# 2020_IST_Respirator_SMD_v3.net
KiCad netlist of a schematic drawn in EAGLE
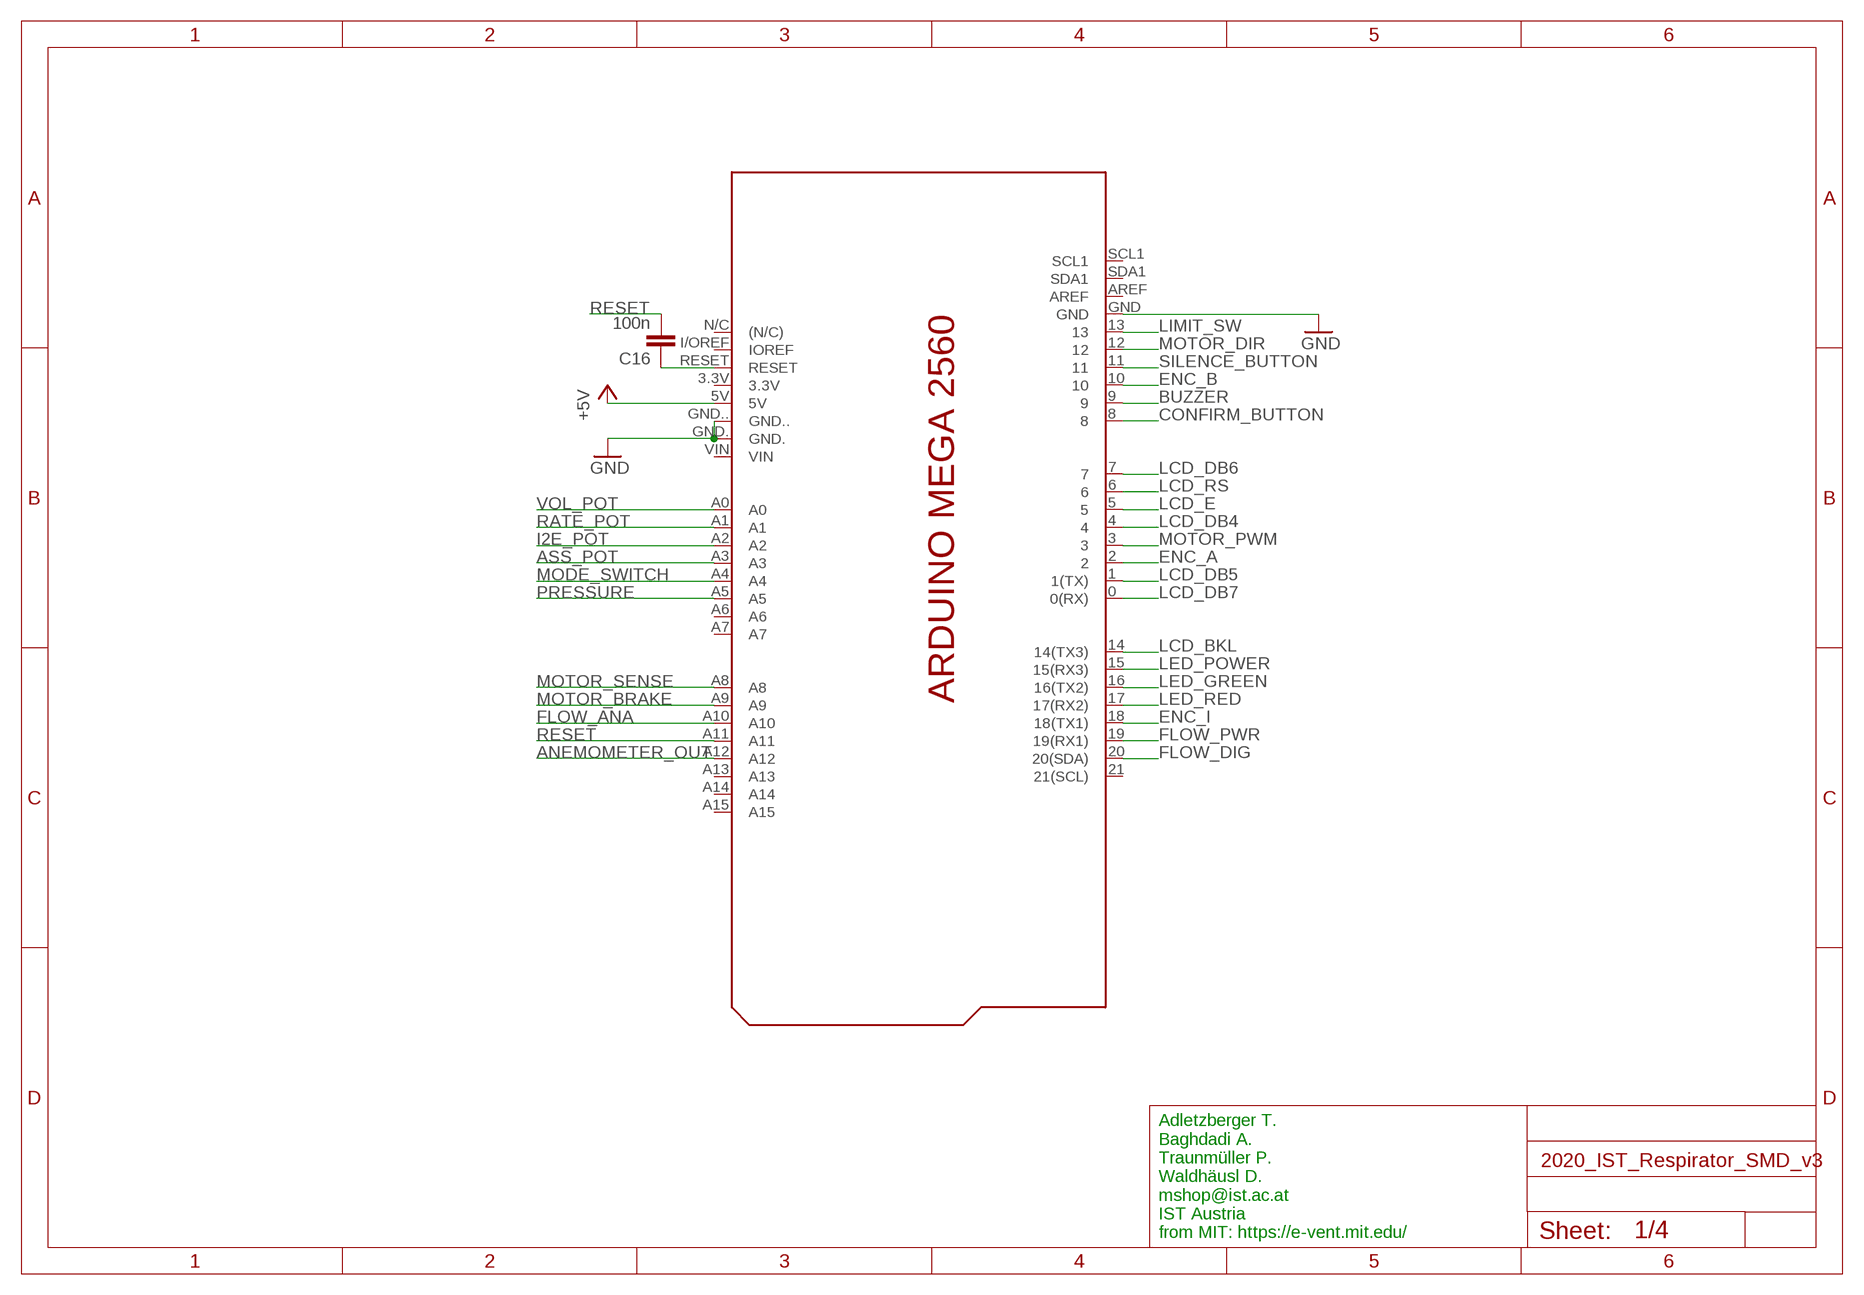
[diagram p0: schematic, sheet 1]
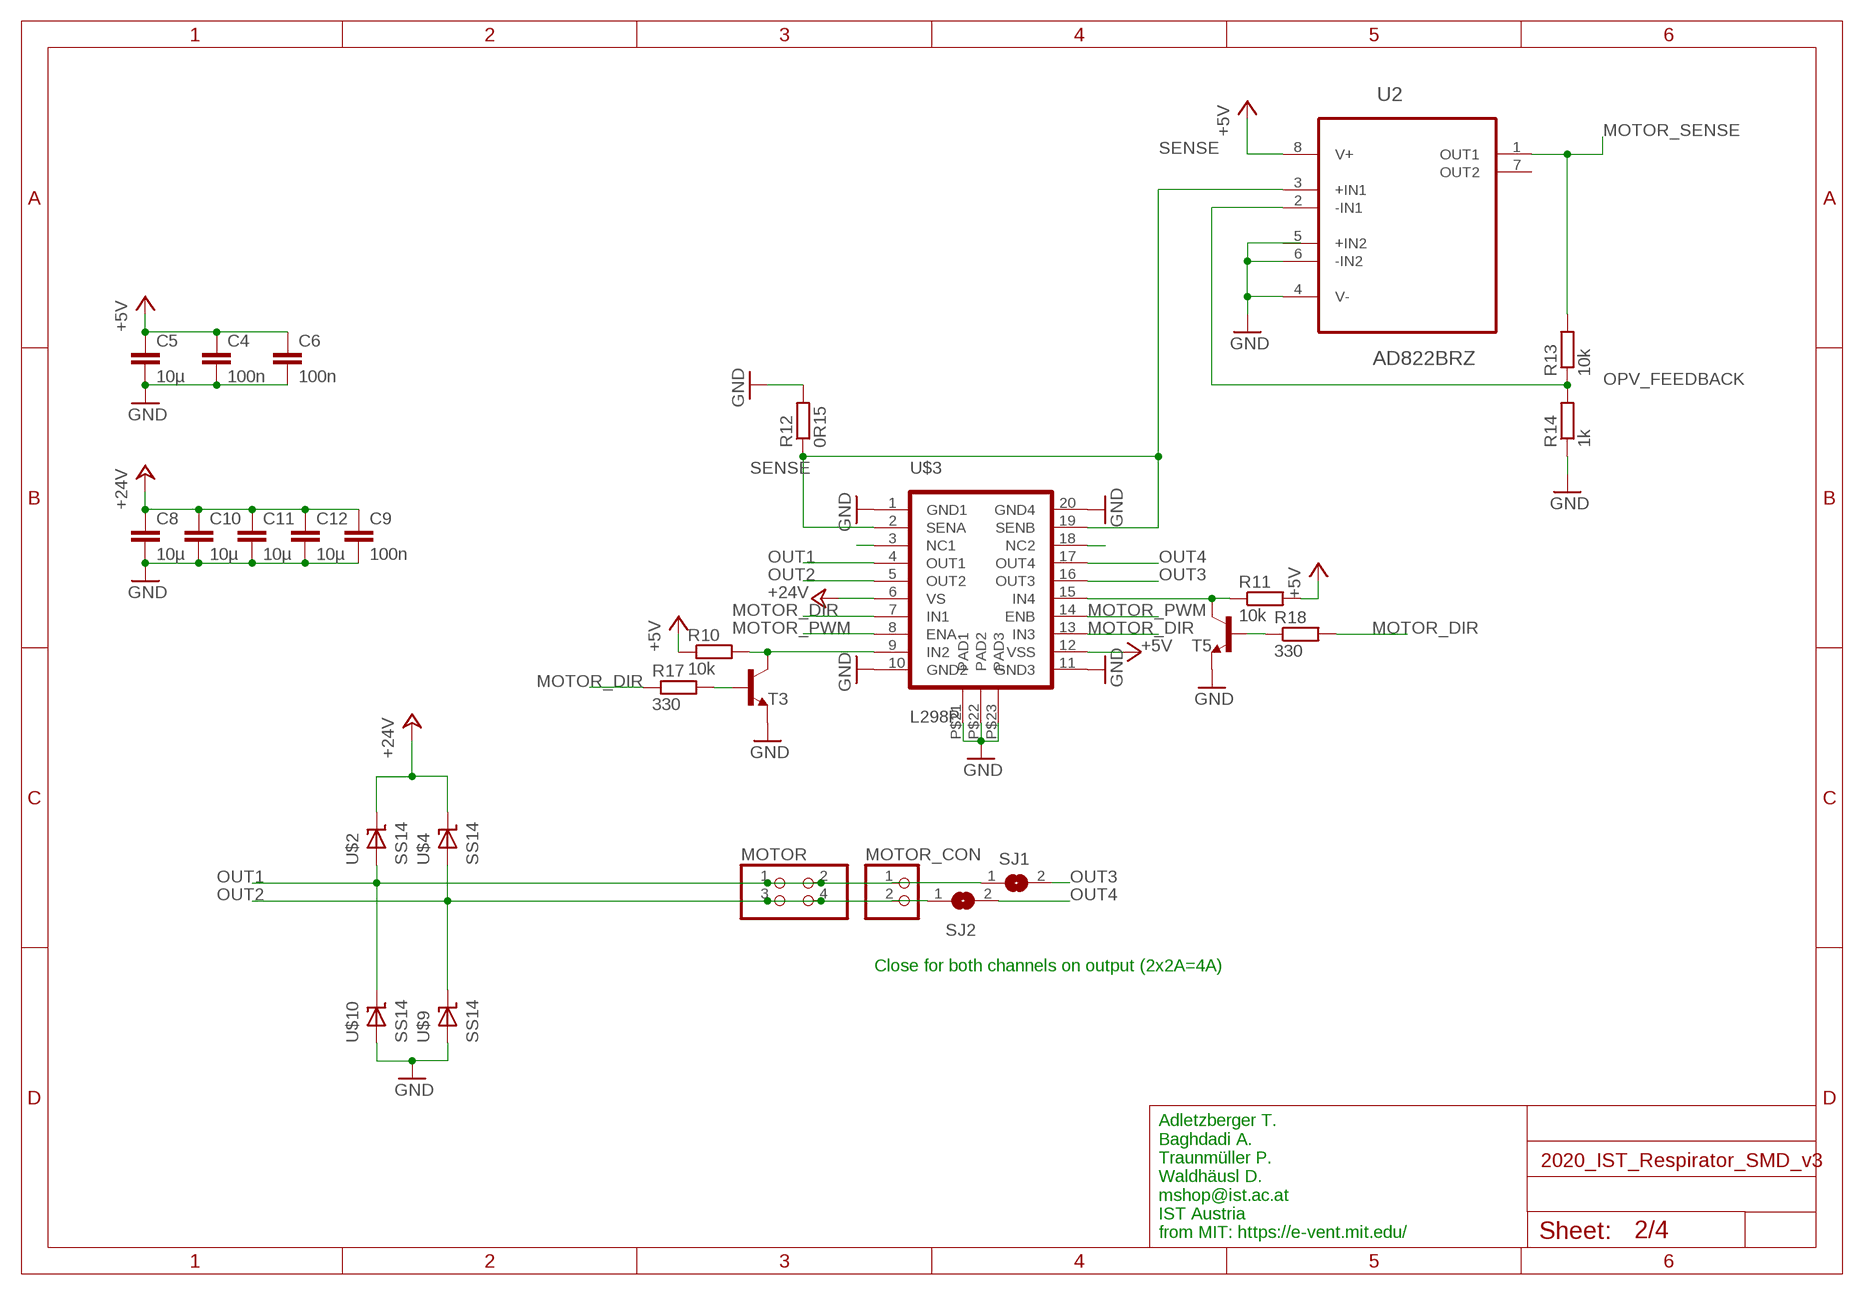
[diagram p1: schematic, sheet 2]
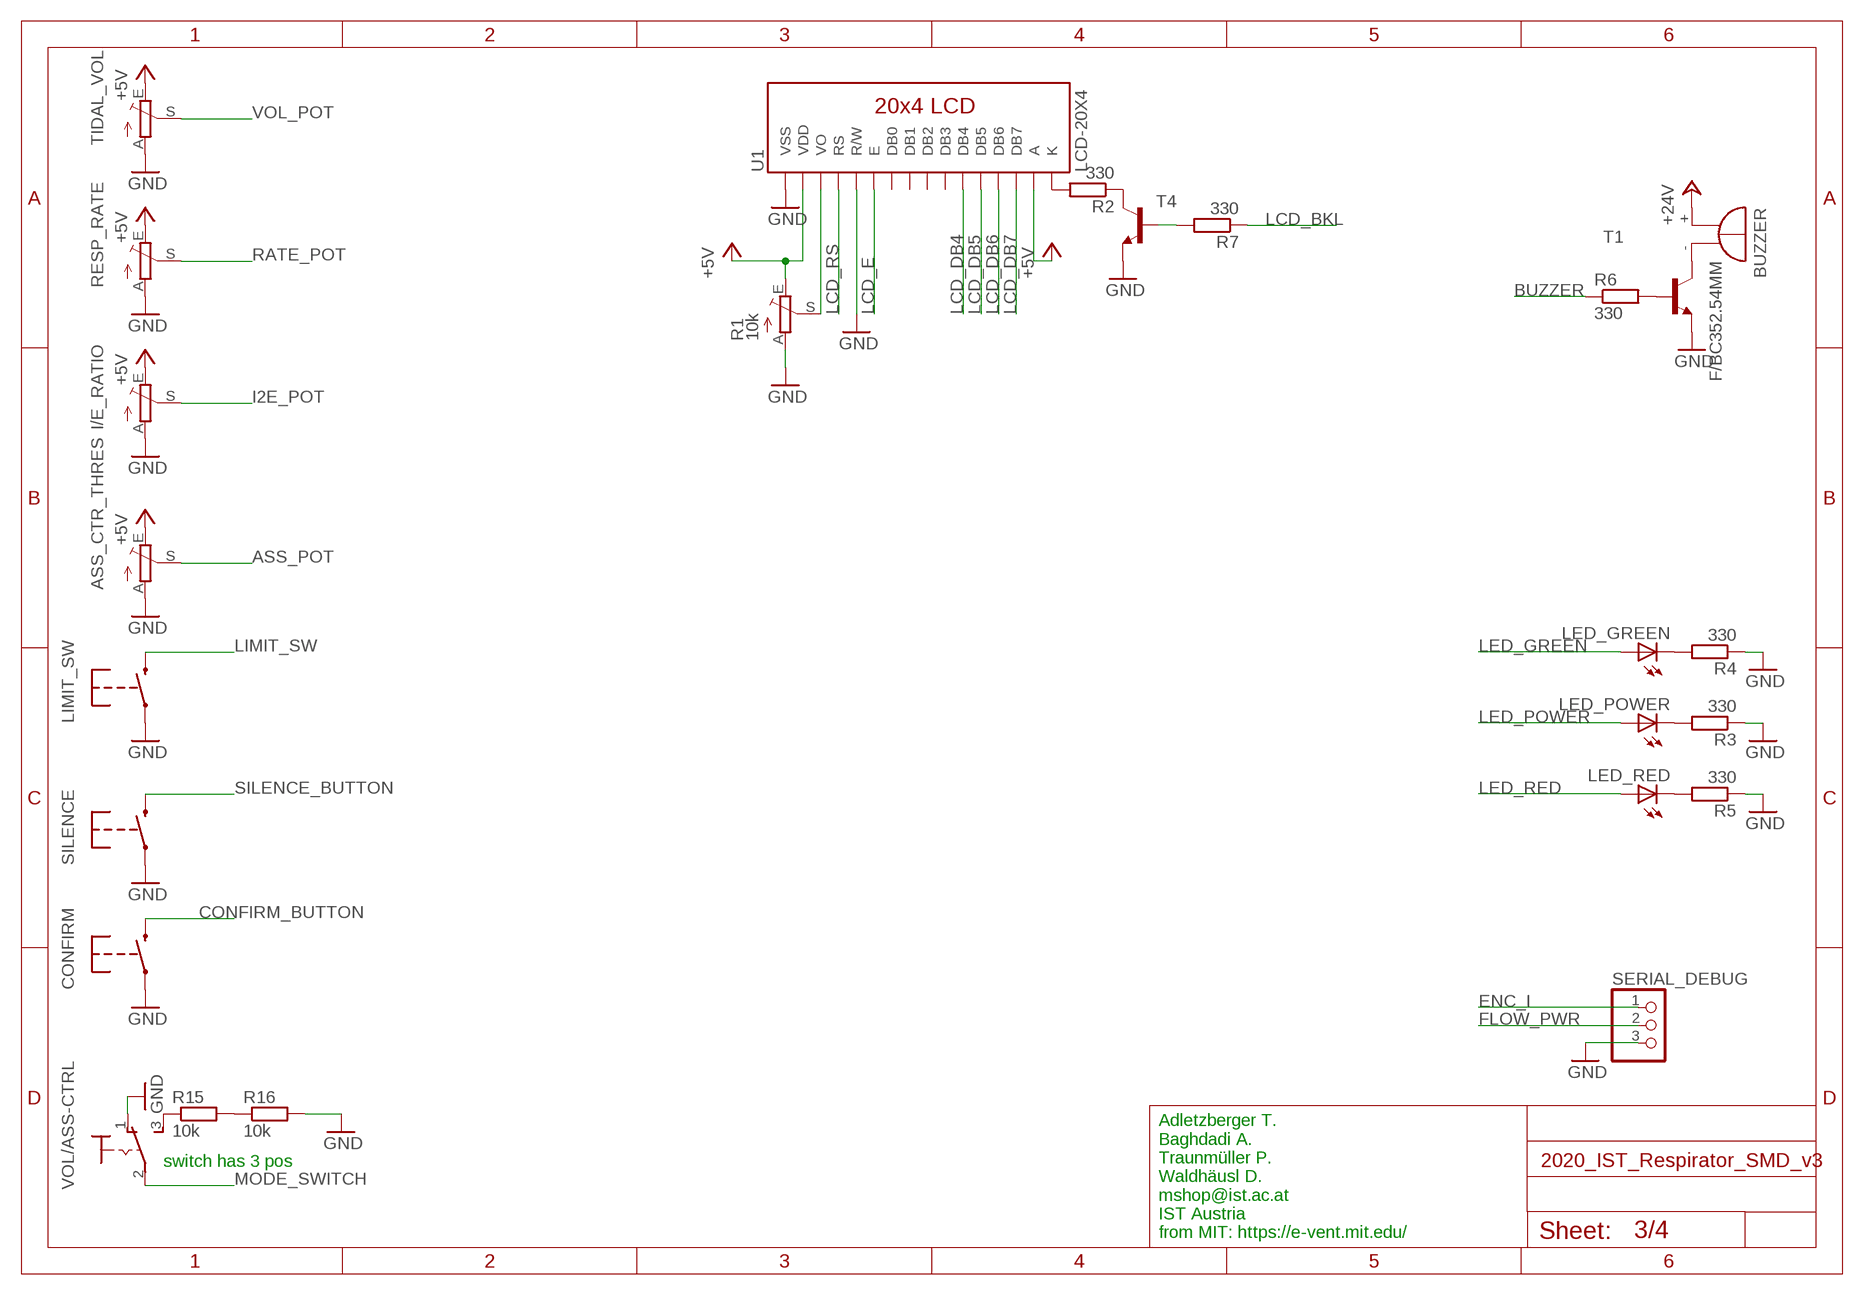
[diagram p2: schematic, sheet 3]
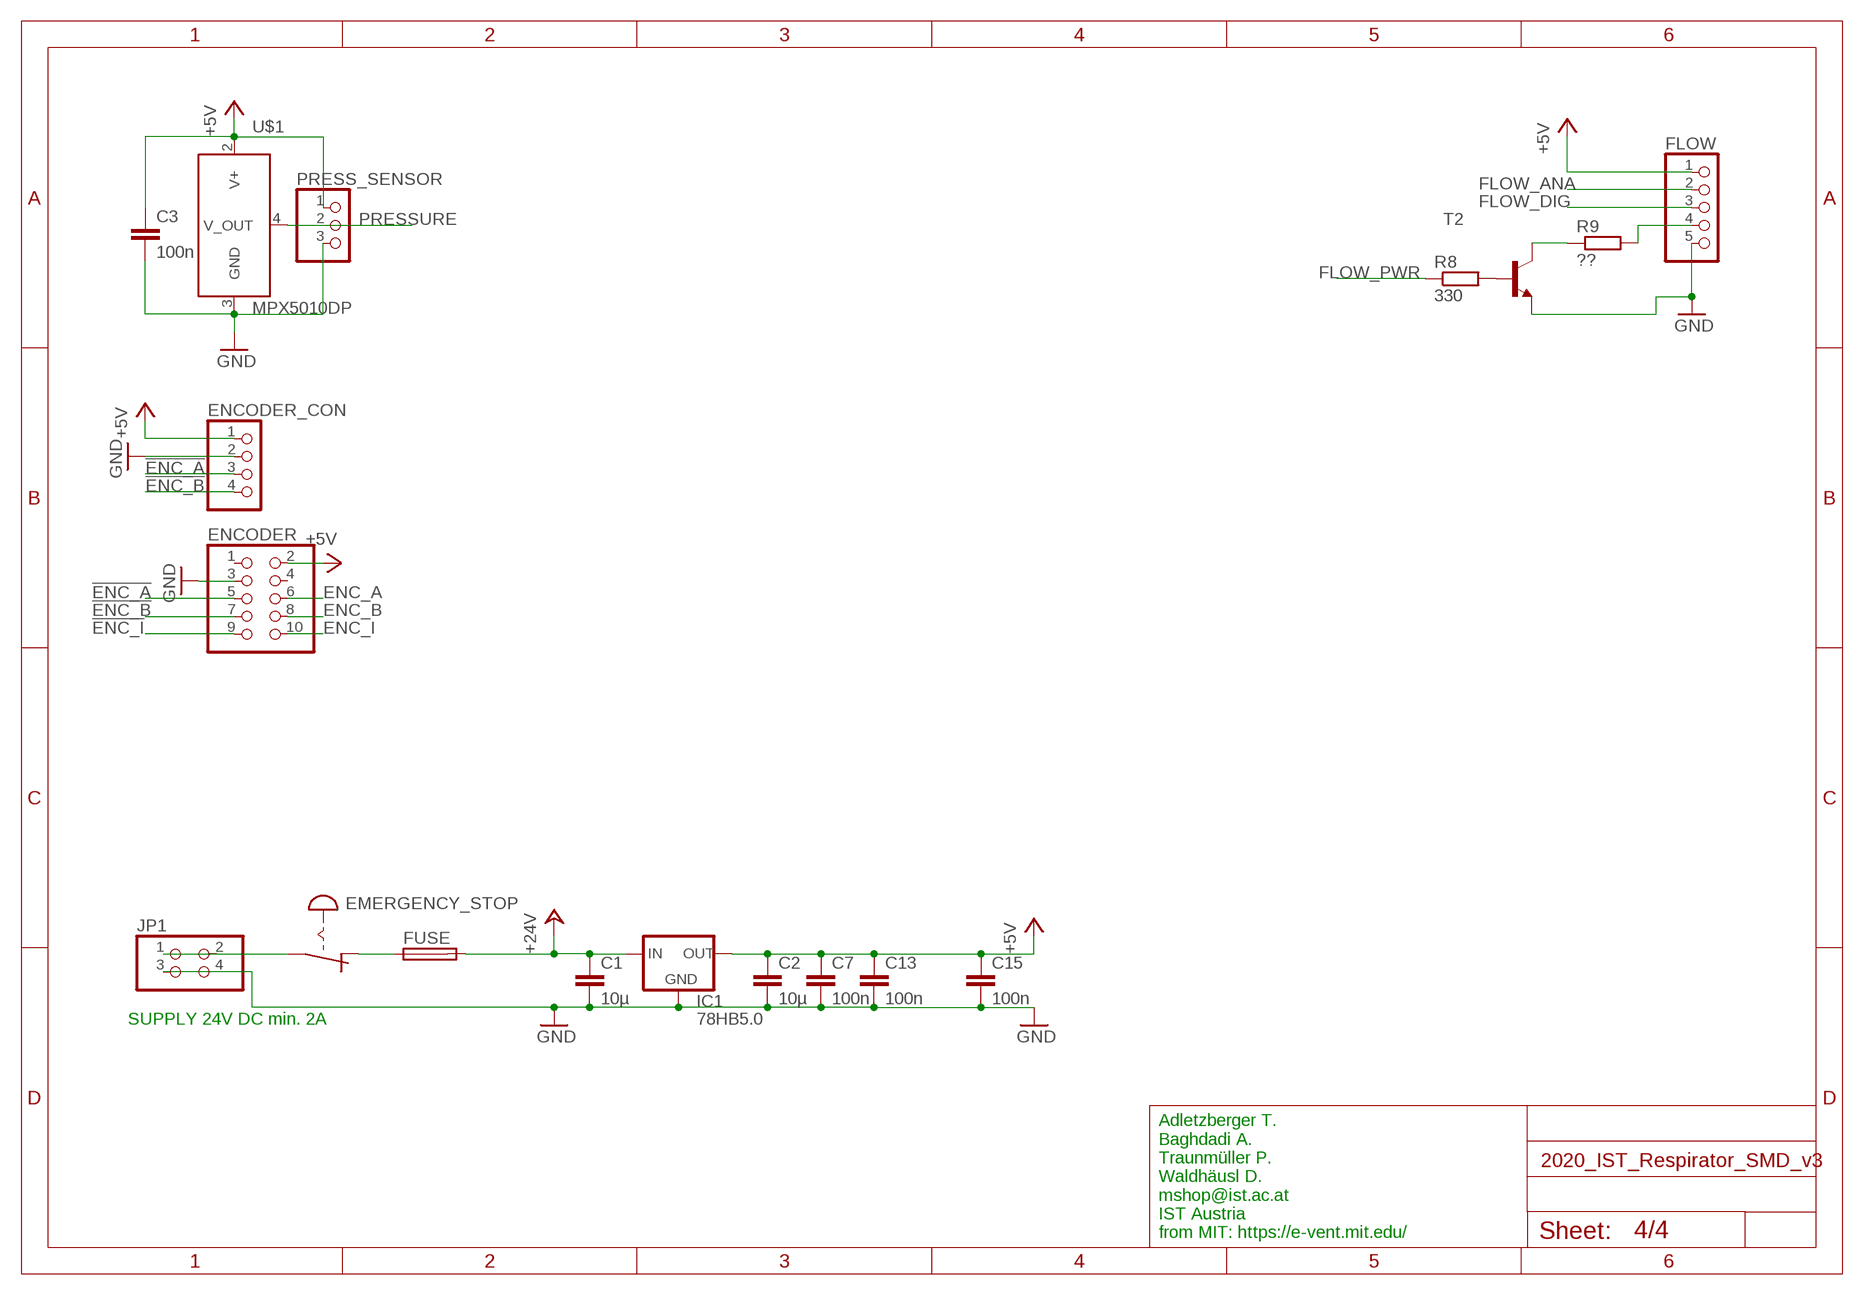
[diagram p3: schematic, sheet 4]

(export (version "E")
  (design (tool "Eeschema 10.0.6"))
  (components
    (comp (ref "ASS_CTR_THRES")
      (value "TRIM_EU-ROUND")
      (footprint "eagle-import:S64W_ROUND-PADS")
      (libsource (lib "eagle-import") (part "TRIM_EU-ROUND"))
    )
    (comp (ref "BUZZER")
      (value "F/BC352.54MM")
      (footprint "eagle-import:F_BC35_2.54MM")
      (libsource (lib "eagle-import") (part "F/BC352.54MM"))
    )
    (comp (ref "CONFIRM")
      (value "SWITCH-MOMENTARY-22.54")
      (footprint "eagle-import:TACTILE-2.54MM")
      (libsource (lib "eagle-import") (part "SWITCH-MOMENTARY-22.54"))
    )
    (comp (ref "I/E_RATIO")
      (value "TRIM_EU-ROUND")
      (footprint "eagle-import:S64W_ROUND-PADS")
      (libsource (lib "eagle-import") (part "TRIM_EU-ROUND"))
    )
    (comp (ref "LED_GREEN")
      (value "LED5MM")
      (footprint "eagle-import:LED5MM")
      (libsource (lib "eagle-import") (part "LED5MM"))
    )
    (comp (ref "LED_POWER")
      (value "LED5MM")
      (footprint "eagle-import:LED5MM")
      (libsource (lib "eagle-import") (part "LED5MM"))
    )
    (comp (ref "LED_RED")
      (value "LED5MM")
      (footprint "eagle-import:LED5MM")
      (libsource (lib "eagle-import") (part "LED5MM"))
    )
    (comp (ref "LIMIT_SW")
      (value "SWITCH-MOMENTARY-22.54")
      (footprint "eagle-import:TACTILE-2.54MM")
      (libsource (lib "eagle-import") (part "SWITCH-MOMENTARY-22.54"))
    )
    (comp (ref "R1")
      (value "10k")
      (footprint "eagle-import:S64W")
      (libsource (lib "eagle-import") (part "TRIM_EU-S64W"))
    )
    (comp (ref "R2")
      (value "330")
      (footprint "eagle-import:R0805")
      (libsource (lib "eagle-import") (part "R-EU_R0805"))
    )
    (comp (ref "R3")
      (value "330")
      (footprint "eagle-import:R0805")
      (libsource (lib "eagle-import") (part "R-EU_R0805"))
    )
    (comp (ref "R4")
      (value "330")
      (footprint "eagle-import:R0805")
      (libsource (lib "eagle-import") (part "R-EU_R0805"))
    )
    (comp (ref "R5")
      (value "330")
      (footprint "eagle-import:R0805")
      (libsource (lib "eagle-import") (part "R-EU_R0805"))
    )
    (comp (ref "R6")
      (value "330")
      (footprint "eagle-import:R0805")
      (libsource (lib "eagle-import") (part "R-EU_R0805"))
    )
    (comp (ref "R7")
      (value "330")
      (footprint "eagle-import:R0805")
      (libsource (lib "eagle-import") (part "R-EU_R0805"))
    )
    (comp (ref "R15")
      (value "10k")
      (footprint "eagle-import:R0805")
      (libsource (lib "eagle-import") (part "R-EU_R0805"))
    )
    (comp (ref "R16")
      (value "10k")
      (footprint "eagle-import:R0805")
      (libsource (lib "eagle-import") (part "R-EU_R0805"))
    )
    (comp (ref "RESP_RATE")
      (value "TRIM_EU-ROUND")
      (footprint "eagle-import:S64W_ROUND-PADS")
      (libsource (lib "eagle-import") (part "TRIM_EU-ROUND"))
    )
    (comp (ref "SERIAL_DEBUG")
      (value "PINHD-1X3")
      (footprint "eagle-import:1X03")
      (libsource (lib "eagle-import") (part "PINHD-1X3"))
    )
    (comp (ref "SILENCE")
      (value "SWITCH-MOMENTARY-22.54")
      (footprint "eagle-import:TACTILE-2.54MM")
      (libsource (lib "eagle-import") (part "SWITCH-MOMENTARY-22.54"))
    )
    (comp (ref "T1")
      (value "MMBT3904LT1-NPN-SOT23-BEC")
      (footprint "eagle-import:SOT23-BEC")
      (libsource (lib "eagle-import") (part "-NPN-SOT23-BECMMBT3904LT1"))
    )
    (comp (ref "T4")
      (value "MMBT3904LT1-NPN-SOT23-BEC")
      (footprint "eagle-import:SOT23-BEC")
      (libsource (lib "eagle-import") (part "-NPN-SOT23-BECMMBT3904LT1"))
    )
    (comp (ref "TIDAL_VOL")
      (value "TRIM_EU-ROUND")
      (footprint "eagle-import:S64W_ROUND-PADS")
      (libsource (lib "eagle-import") (part "TRIM_EU-ROUND"))
    )
    (comp (ref "U1")
      (value "LCD-20X4")
      (footprint "eagle-import:LCD-20X4")
      (libsource (lib "eagle-import") (part "LCD-20X4"))
    )
    (comp (ref "VOL/ASS-CTRL")
      (value "320-9162.54MM-ROUND-PADS")
      (footprint "eagle-import:320-916_2.54MM_ROUND-PADS")
      (libsource (lib "eagle-import") (part "320-9162.54MM-ROUND-PADS"))
    )
    (comp (ref "C4")
      (value "100n")
      (footprint "eagle-import:C0805")
      (libsource (lib "eagle-import") (part "C-EUC0805"))
    )
    (comp (ref "C5")
      (value "10µ")
      (footprint "eagle-import:C1210")
      (libsource (lib "eagle-import") (part "C-EUC1210"))
    )
    (comp (ref "C6")
      (value "100n")
      (footprint "eagle-import:C0805")
      (libsource (lib "eagle-import") (part "C-EUC0805"))
    )
    (comp (ref "C8")
      (value "10µ")
      (footprint "eagle-import:C1210")
      (libsource (lib "eagle-import") (part "C-EUC1210"))
    )
    (comp (ref "C9")
      (value "100n")
      (footprint "eagle-import:C0805")
      (libsource (lib "eagle-import") (part "C-EUC0805"))
    )
    (comp (ref "C10")
      (value "10µ")
      (footprint "eagle-import:C1210")
      (libsource (lib "eagle-import") (part "C-EUC1210"))
    )
    (comp (ref "C11")
      (value "10µ")
      (footprint "eagle-import:C1210")
      (libsource (lib "eagle-import") (part "C-EUC1210"))
    )
    (comp (ref "C12")
      (value "10µ")
      (footprint "eagle-import:C1210")
      (libsource (lib "eagle-import") (part "C-EUC1210"))
    )
    (comp (ref "MOTOR")
      (value "PINHD-2X2")
      (footprint "eagle-import:2X02")
      (libsource (lib "eagle-import") (part "PINHD-2X2"))
    )
    (comp (ref "MOTOR_CON")
      (value "PINHD-1X2_3.93MM")
      (footprint "eagle-import:1X02_3.96MM")
      (libsource (lib "eagle-import") (part "PINHD-1X2_3.93MM"))
    )
    (comp (ref "R10")
      (value "10k")
      (footprint "eagle-import:R0805")
      (libsource (lib "eagle-import") (part "R-EU_R0805"))
    )
    (comp (ref "R11")
      (value "10k")
      (footprint "eagle-import:R0805")
      (libsource (lib "eagle-import") (part "R-EU_R0805"))
    )
    (comp (ref "R12")
      (value "0R15")
      (footprint "eagle-import:R1206")
      (libsource (lib "eagle-import") (part "R-EU_R1206"))
    )
    (comp (ref "R13")
      (value "10k")
      (footprint "eagle-import:R0805")
      (libsource (lib "eagle-import") (part "R-EU_R0805"))
    )
    (comp (ref "R14")
      (value "1k")
      (footprint "eagle-import:R0805")
      (libsource (lib "eagle-import") (part "R-EU_R0805"))
    )
    (comp (ref "R17")
      (value "330")
      (footprint "eagle-import:R0805")
      (libsource (lib "eagle-import") (part "R-EU_R0805"))
    )
    (comp (ref "R18")
      (value "330")
      (footprint "eagle-import:R0805")
      (libsource (lib "eagle-import") (part "R-EU_R0805"))
    )
    (comp (ref "SJ1") (value "SJ") (footprint "eagle-import:SJ") (libsource (lib "eagle-import") (part "SJ")))
    (comp (ref "SJ2") (value "SJ") (footprint "eagle-import:SJ") (libsource (lib "eagle-import") (part "SJ")))
    (comp (ref "T3")
      (value "MMBT3904LT1-NPN-SOT23-BEC")
      (footprint "eagle-import:SOT23-BEC")
      (libsource (lib "eagle-import") (part "-NPN-SOT23-BECMMBT3904LT1"))
    )
    (comp (ref "T5")
      (value "MMBT3904LT1-NPN-SOT23-BEC")
      (footprint "eagle-import:SOT23-BEC")
      (libsource (lib "eagle-import") (part "-NPN-SOT23-BECMMBT3904LT1"))
    )
    (comp (ref "U$2")
      (value "SS14")
      (footprint "eagle-import:SMA")
      (libsource (lib "eagle-import") (part "SS14"))
    )
    (comp (ref "U$3")
      (value "L298P")
      (footprint "eagle-import:POWER-SO20")
      (libsource (lib "eagle-import") (part "L298P"))
    )
    (comp (ref "U$4")
      (value "SS14")
      (footprint "eagle-import:SMA")
      (libsource (lib "eagle-import") (part "SS14"))
    )
    (comp (ref "U$9")
      (value "SS14")
      (footprint "eagle-import:SMA")
      (libsource (lib "eagle-import") (part "SS14"))
    )
    (comp (ref "U$10")
      (value "SS14")
      (footprint "eagle-import:SMA")
      (libsource (lib "eagle-import") (part "SS14"))
    )
    (comp (ref "U2")
      (value "AD822BRZ")
      (footprint "eagle-import:SOIC127P600X175-8N")
      (libsource (lib "eagle-import") (part "AD822BRZ"))
    )
    (comp (ref "C1")
      (value "10µ")
      (footprint "eagle-import:C1210")
      (libsource (lib "eagle-import") (part "C-EUC1210"))
    )
    (comp (ref "C2")
      (value "10µ")
      (footprint "eagle-import:C1210")
      (libsource (lib "eagle-import") (part "C-EUC1210"))
    )
    (comp (ref "C3")
      (value "100n")
      (footprint "eagle-import:C0805")
      (libsource (lib "eagle-import") (part "C-EUC0805"))
    )
    (comp (ref "C7")
      (value "100n")
      (footprint "eagle-import:C0805")
      (libsource (lib "eagle-import") (part "C-EUC0805"))
    )
    (comp (ref "C13")
      (value "100n")
      (footprint "eagle-import:C0805")
      (libsource (lib "eagle-import") (part "C-EUC0805"))
    )
    (comp (ref "C15")
      (value "100n")
      (footprint "eagle-import:C0805")
      (libsource (lib "eagle-import") (part "C-EUC0805"))
    )
    (comp (ref "EMERGENCY_STOP")
      (value "EMERGENCY_STOP")
      (footprint "eagle-import:320-916_2.54MM_ROUND-PAD_2PINS")
      (libsource (lib "eagle-import") (part "EMERGENCY_STOP"))
    )
    (comp (ref "ENCODER")
      (value "PINHD-2X5")
      (footprint "eagle-import:2X05")
      (libsource (lib "eagle-import") (part "PINHD-2X5"))
    )
    (comp (ref "ENCODER_CON")
      (value "PINHD-1X42MM")
      (footprint "eagle-import:1_04X2MM")
      (libsource (lib "eagle-import") (part "PINHD-1X42MM"))
    )
    (comp (ref "FLOW")
      (value "PINHD-1X5")
      (footprint "eagle-import:1X05")
      (libsource (lib "eagle-import") (part "PINHD-1X5"))
    )
    (comp (ref "FUSE")
      (value "SH22,5")
      (footprint "eagle-import:SH22,5")
      (fields (field (name "MF") "SCHURTER") (field (name "MPN") "0031.8201"))
      (libsource (lib "eagle-import") (part "SH22,5"))
    )
    (comp (ref "IC1")
      (value "78HB5.0")
      (footprint "eagle-import:R-78HB")
      (libsource (lib "eagle-import") (part "78XXS"))
    )
    (comp (ref "JP1")
      (value "PINHD-2X2")
      (footprint "eagle-import:2X02")
      (libsource (lib "eagle-import") (part "PINHD-2X2"))
    )
    (comp (ref "PRESS_SENSOR")
      (value "PINHD-1X3")
      (footprint "eagle-import:1X03")
      (libsource (lib "eagle-import") (part "PINHD-1X3"))
    )
    (comp (ref "R8")
      (value "330")
      (footprint "eagle-import:R0805")
      (libsource (lib "eagle-import") (part "R-EU_R0805"))
    )
    (comp (ref "R9")
      (value "??")
      (footprint "eagle-import:R0805")
      (libsource (lib "eagle-import") (part "R-EU_R0805"))
    )
    (comp (ref "T2")
      (value "MMBT3904LT1-NPN-SOT23-BEC")
      (footprint "eagle-import:SOT23-BEC")
      (libsource (lib "eagle-import") (part "-NPN-SOT23-BECMMBT3904LT1"))
    )
    (comp (ref "U$1")
      (value "MPX5010DP")
      (footprint "eagle-import:MPX5010DP_SOP482")
      (libsource (lib "eagle-import") (part "MPX5010DP"))
    )
    (comp (ref "C16")
      (value "100n")
      (footprint "eagle-import:C0805")
      (libsource (lib "eagle-import") (part "C-EUC0805"))
    )
    (comp (ref "PCB1")
      (value "ARDUINO_MEGA2560_NOTALLPINS")
      (footprint "eagle-import:ARDUINO_MEGA2560_NOTALLPINS")
      (libsource (lib "eagle-import") (part "ARDUINO_MEGA2560_NOTALLPINS"))
    )
  )
  (nets
    (net (code "1") (name "+5V") (class "Default")
      (node (ref "ASS_CTR_THRES") (pin "E") (pinfunction "E_E") (pintype "passive"))
      (node (ref "C13") (pin "1") (pinfunction "1_1") (pintype "passive"))
      (node (ref "C15") (pin "1") (pinfunction "1_1") (pintype "passive"))
      (node (ref "C2") (pin "1") (pinfunction "1_1") (pintype "passive"))
      (node (ref "C3") (pin "1") (pinfunction "1_1") (pintype "passive"))
      (node (ref "C4") (pin "1") (pinfunction "1_1") (pintype "passive"))
      (node (ref "C5") (pin "1") (pinfunction "1_1") (pintype "passive"))
      (node (ref "C6") (pin "1") (pinfunction "1_1") (pintype "passive"))
      (node (ref "C7") (pin "1") (pinfunction "1_1") (pintype "passive"))
      (node (ref "ENCODER") (pin "2") (pinfunction "2_2") (pintype "passive"))
      (node (ref "ENCODER_CON") (pin "1") (pinfunction "1_1") (pintype "passive"))
      (node (ref "FLOW") (pin "1") (pinfunction "1_1") (pintype "passive"))
      (node (ref "I/E_RATIO") (pin "E") (pinfunction "E_E") (pintype "passive"))
      (node (ref "IC1") (pin "OUT") (pinfunction "OUT_OUT") (pintype "passive"))
      (node (ref "PCB1") (pin "5V") (pinfunction "5V_5V") (pintype "bidirectional"))
      (node (ref "PRESS_SENSOR") (pin "1") (pinfunction "1_1") (pintype "passive"))
      (node (ref "R1") (pin "E") (pinfunction "E_E") (pintype "passive"))
      (node (ref "R10") (pin "1") (pinfunction "1_1") (pintype "passive"))
      (node (ref "R11") (pin "2") (pinfunction "2_2") (pintype "passive"))
      (node (ref "RESP_RATE") (pin "E") (pinfunction "E_E") (pintype "passive"))
      (node (ref "TIDAL_VOL") (pin "E") (pinfunction "E_E") (pintype "passive"))
      (node (ref "U$1") (pin "2") (pinfunction "V+_2") (pintype "power_in"))
      (node (ref "U$3") (pin "P$12") (pinfunction "VSS_P$12") (pintype "power_in"))
      (node (ref "U1") (pin "15") (pinfunction "A_15") (pintype "power_in"))
      (node (ref "U1") (pin "2") (pinfunction "VDD_2") (pintype "power_in"))
      (node (ref "U2") (pin "8") (pinfunction "V+_8") (pintype "power_in"))
    )
    (net (code "2") (name "+24V") (class "Default")
      (node (ref "BUZZER") (pin "+") (pinfunction "+_+") (pintype "passive"))
      (node (ref "C1") (pin "1") (pinfunction "1_1") (pintype "passive"))
      (node (ref "C10") (pin "1") (pinfunction "1_1") (pintype "passive"))
      (node (ref "C11") (pin "1") (pinfunction "1_1") (pintype "passive"))
      (node (ref "C12") (pin "1") (pinfunction "1_1") (pintype "passive"))
      (node (ref "C8") (pin "1") (pinfunction "1_1") (pintype "passive"))
      (node (ref "C9") (pin "1") (pinfunction "1_1") (pintype "passive"))
      (node (ref "FUSE") (pin "2") (pinfunction "2_2") (pintype "passive"))
      (node (ref "IC1") (pin "IN") (pinfunction "IN_IN") (pintype "input"))
      (node (ref "U$2") (pin "P$1") (pinfunction "K_P$1") (pintype "bidirectional"))
      (node (ref "U$3") (pin "P$6") (pinfunction "VS_P$6") (pintype "power_in"))
      (node (ref "U$4") (pin "P$1") (pinfunction "K_P$1") (pintype "bidirectional"))
    )
    (net (code "3") (name "ANEMOMETER_OUT") (class "Default")
      (node (ref "PCB1") (pin "A12") (pinfunction "A12_A12") (pintype "bidirectional"))
    )
    (net (code "4") (name "ASS_POT") (class "Default")
      (node (ref "ASS_CTR_THRES") (pin "S") (pinfunction "S_S") (pintype "passive"))
      (node (ref "PCB1") (pin "A3") (pinfunction "A3_A3") (pintype "bidirectional"))
    )
    (net (code "5") (name "BUZZER") (class "Default")
      (node (ref "PCB1") (pin "9") (pinfunction "9_9") (pintype "bidirectional"))
      (node (ref "R6") (pin "1") (pinfunction "1_1") (pintype "passive"))
    )
    (net (code "6") (name "CONFIRM_BUTTON") (class "Default")
      (node (ref "CONFIRM") (pin "3") (pinfunction "2_3") (pintype "passive"))
      (node (ref "PCB1") (pin "8") (pinfunction "8_8") (pintype "bidirectional"))
    )
    (net (code "7") (name "ENC_A") (class "Default")
      (node (ref "ENCODER") (pin "6") (pinfunction "6_6") (pintype "passive"))
      (node (ref "PCB1") (pin "2") (pinfunction "2_2") (pintype "bidirectional"))
    )
    (net (code "8") (name "ENC_B") (class "Default")
      (node (ref "ENCODER") (pin "8") (pinfunction "8_8") (pintype "passive"))
      (node (ref "PCB1") (pin "10") (pinfunction "10_10") (pintype "bidirectional"))
    )
    (net (code "9") (name "ENC_I") (class "Default")
      (node (ref "ENCODER") (pin "10") (pinfunction "10_10") (pintype "passive"))
      (node (ref "PCB1") (pin "18") (pinfunction "18(TX1)_18") (pintype "bidirectional"))
      (node (ref "SERIAL_DEBUG") (pin "1") (pinfunction "1_1") (pintype "passive"))
    )
    (net (code "10") (name "FLOW_ANA") (class "Default")
      (node (ref "FLOW") (pin "2") (pinfunction "2_2") (pintype "passive"))
      (node (ref "PCB1") (pin "A10") (pinfunction "A10_A10") (pintype "bidirectional"))
    )
    (net (code "11") (name "FLOW_DIG") (class "Default")
      (node (ref "FLOW") (pin "3") (pinfunction "3_3") (pintype "passive"))
      (node (ref "PCB1") (pin "20") (pinfunction "20(SDA)_20") (pintype "bidirectional"))
    )
    (net (code "12") (name "FLOW_PWR") (class "Default")
      (node (ref "PCB1") (pin "19") (pinfunction "19(RX1)_19") (pintype "bidirectional"))
      (node (ref "R8") (pin "1") (pinfunction "1_1") (pintype "passive"))
      (node (ref "SERIAL_DEBUG") (pin "2") (pinfunction "2_2") (pintype "passive"))
    )
    (net (code "13") (name "GND") (class "Default")
      (node (ref "ASS_CTR_THRES") (pin "A") (pinfunction "A_A") (pintype "passive"))
      (node (ref "C1") (pin "2") (pinfunction "2_2") (pintype "passive"))
      (node (ref "C10") (pin "2") (pinfunction "2_2") (pintype "passive"))
      (node (ref "C11") (pin "2") (pinfunction "2_2") (pintype "passive"))
      (node (ref "C12") (pin "2") (pinfunction "2_2") (pintype "passive"))
      (node (ref "C13") (pin "2") (pinfunction "2_2") (pintype "passive"))
      (node (ref "C15") (pin "2") (pinfunction "2_2") (pintype "passive"))
      (node (ref "C2") (pin "2") (pinfunction "2_2") (pintype "passive"))
      (node (ref "C3") (pin "2") (pinfunction "2_2") (pintype "passive"))
      (node (ref "C4") (pin "2") (pinfunction "2_2") (pintype "passive"))
      (node (ref "C5") (pin "2") (pinfunction "2_2") (pintype "passive"))
      (node (ref "C6") (pin "2") (pinfunction "2_2") (pintype "passive"))
      (node (ref "C7") (pin "2") (pinfunction "2_2") (pintype "passive"))
      (node (ref "C8") (pin "2") (pinfunction "2_2") (pintype "passive"))
      (node (ref "C9") (pin "2") (pinfunction "2_2") (pintype "passive"))
      (node (ref "CONFIRM") (pin "1") (pinfunction "1_1") (pintype "passive"))
      (node (ref "ENCODER") (pin "3") (pinfunction "3_3") (pintype "passive"))
      (node (ref "ENCODER_CON") (pin "2") (pinfunction "2_2") (pintype "passive"))
      (node (ref "FLOW") (pin "5") (pinfunction "5_5") (pintype "passive"))
      (node (ref "I/E_RATIO") (pin "A") (pinfunction "A_A") (pintype "passive"))
      (node (ref "IC1") (pin "GND") (pinfunction "GND_GND") (pintype "input"))
      (node (ref "JP1") (pin "3") (pinfunction "3_3") (pintype "passive"))
      (node (ref "JP1") (pin "4") (pinfunction "4_4") (pintype "passive"))
      (node (ref "LIMIT_SW") (pin "1") (pinfunction "1_1") (pintype "passive"))
      (node (ref "PCB1") (pin "GND") (pinfunction "GND_GND") (pintype "bidirectional"))
      (node (ref "PCB1") (pin "GND.") (pinfunction "GND._GND.") (pintype "bidirectional"))
      (node (ref "PCB1") (pin "GND..") (pinfunction "GND.._GND..") (pintype "bidirectional"))
      (node (ref "PRESS_SENSOR") (pin "3") (pinfunction "3_3") (pintype "passive"))
      (node (ref "R1") (pin "A") (pinfunction "A_A") (pintype "passive"))
      (node (ref "R12") (pin "2") (pinfunction "2_2") (pintype "passive"))
      (node (ref "R14") (pin "1") (pinfunction "1_1") (pintype "passive"))
      (node (ref "R16") (pin "2") (pinfunction "2_2") (pintype "passive"))
      (node (ref "R3") (pin "1") (pinfunction "1_1") (pintype "passive"))
      (node (ref "R4") (pin "1") (pinfunction "1_1") (pintype "passive"))
      (node (ref "R5") (pin "1") (pinfunction "1_1") (pintype "passive"))
      (node (ref "RESP_RATE") (pin "A") (pinfunction "A_A") (pintype "passive"))
      (node (ref "SERIAL_DEBUG") (pin "3") (pinfunction "3_3") (pintype "passive"))
      (node (ref "SILENCE") (pin "1") (pinfunction "1_1") (pintype "passive"))
      (node (ref "T1") (pin "E") (pinfunction "E_E") (pintype "passive"))
      (node (ref "T2") (pin "E") (pinfunction "E_E") (pintype "passive"))
      (node (ref "T3") (pin "E") (pinfunction "E_E") (pintype "passive"))
      (node (ref "T4") (pin "E") (pinfunction "E_E") (pintype "passive"))
      (node (ref "T5") (pin "E") (pinfunction "E_E") (pintype "passive"))
      (node (ref "TIDAL_VOL") (pin "A") (pinfunction "A_A") (pintype "passive"))
      (node (ref "U$1") (pin "3") (pinfunction "GND_3") (pintype "bidirectional"))
      (node (ref "U$10") (pin "P$2") (pinfunction "A_P$2") (pintype "bidirectional"))
      (node (ref "U$3") (pin "P$1") (pinfunction "GND1_P$1") (pintype "power_in"))
      (node (ref "U$3") (pin "P$10") (pinfunction "GND2_P$10") (pintype "power_in"))
      (node (ref "U$3") (pin "P$11") (pinfunction "GND3_P$11") (pintype "power_in"))
      (node (ref "U$3") (pin "P$20") (pinfunction "GND4_P$20") (pintype "power_in"))
      (node (ref "U$3") (pin "P$21") (pinfunction "PAD1_P$21") (pintype "passive"))
      (node (ref "U$3") (pin "P$22") (pinfunction "PAD2_P$22") (pintype "passive"))
      (node (ref "U$3") (pin "P$23") (pinfunction "PAD3_P$23") (pintype "passive"))
      (node (ref "U$9") (pin "P$2") (pinfunction "A_P$2") (pintype "bidirectional"))
      (node (ref "U1") (pin "1") (pinfunction "VSS_1") (pintype "power_in"))
      (node (ref "U1") (pin "5") (pinfunction "R/W_5") (pintype "input"))
      (node (ref "U2") (pin "4") (pinfunction "V-_4") (pintype "power_in"))
      (node (ref "U2") (pin "6") (pinfunction "-IN2_6") (pintype "input"))
      (node (ref "VOL/ASS-CTRL") (pin "1") (pinfunction "O_1") (pintype "passive"))
    )
    (net (code "14") (name "I2E_POT") (class "Default")
      (node (ref "I/E_RATIO") (pin "S") (pinfunction "S_S") (pintype "passive"))
      (node (ref "PCB1") (pin "A2") (pinfunction "A2_A2") (pintype "bidirectional"))
    )
    (net (code "15") (name "LCD_BKL") (class "Default")
      (node (ref "PCB1") (pin "14") (pinfunction "14(TX3)_14") (pintype "bidirectional"))
      (node (ref "R7") (pin "1") (pinfunction "1_1") (pintype "passive"))
    )
    (net (code "16") (name "LCD_DB4") (class "Default")
      (node (ref "PCB1") (pin "4") (pinfunction "4_4") (pintype "bidirectional"))
      (node (ref "U1") (pin "11") (pinfunction "DB4_11") (pintype "bidirectional"))
    )
    (net (code "17") (name "LCD_DB5") (class "Default")
      (node (ref "PCB1") (pin "1") (pinfunction "1(TX)_1") (pintype "bidirectional"))
      (node (ref "U1") (pin "12") (pinfunction "DB5_12") (pintype "bidirectional"))
    )
    (net (code "18") (name "LCD_DB6") (class "Default")
      (node (ref "PCB1") (pin "7") (pinfunction "7_7") (pintype "bidirectional"))
      (node (ref "U1") (pin "13") (pinfunction "DB6_13") (pintype "bidirectional"))
    )
    (net (code "19") (name "LCD_DB7") (class "Default")
      (node (ref "PCB1") (pin "0") (pinfunction "0(RX)_0") (pintype "bidirectional"))
      (node (ref "U1") (pin "14") (pinfunction "DB7_14") (pintype "bidirectional"))
    )
    (net (code "20") (name "LCD_E") (class "Default")
      (node (ref "PCB1") (pin "5") (pinfunction "5_5") (pintype "bidirectional"))
      (node (ref "U1") (pin "6") (pinfunction "E_6") (pintype "input"))
    )
    (net (code "21") (name "LCD_RS") (class "Default")
      (node (ref "PCB1") (pin "6") (pinfunction "6_6") (pintype "bidirectional"))
      (node (ref "U1") (pin "4") (pinfunction "RS_4") (pintype "input"))
    )
    (net (code "22") (name "LED_GREEN") (class "Default")
      (node (ref "LED_GREEN") (pin "A") (pinfunction "A_A") (pintype "passive"))
      (node (ref "PCB1") (pin "16") (pinfunction "16(TX2)_16") (pintype "bidirectional"))
    )
    (net (code "23") (name "LED_POWER") (class "Default")
      (node (ref "LED_POWER") (pin "A") (pinfunction "A_A") (pintype "passive"))
      (node (ref "PCB1") (pin "15") (pinfunction "15(RX3)_15") (pintype "bidirectional"))
    )
    (net (code "24") (name "LED_RED") (class "Default")
      (node (ref "LED_RED") (pin "A") (pinfunction "A_A") (pintype "passive"))
      (node (ref "PCB1") (pin "17") (pinfunction "17(RX2)_17") (pintype "bidirectional"))
    )
    (net (code "25") (name "LIMIT_SW") (class "Default")
      (node (ref "LIMIT_SW") (pin "3") (pinfunction "2_3") (pintype "passive"))
      (node (ref "PCB1") (pin "13") (pinfunction "13_13") (pintype "bidirectional"))
    )
    (net (code "26") (name "MODE_SWITCH") (class "Default")
      (node (ref "PCB1") (pin "A4") (pinfunction "A4_A4") (pintype "bidirectional"))
      (node (ref "VOL/ASS-CTRL") (pin "2") (pinfunction "P_2") (pintype "passive"))
    )
    (net (code "27") (name "MOTOR_BRAKE") (class "Default")
      (node (ref "PCB1") (pin "A9") (pinfunction "A9_A9") (pintype "bidirectional"))
    )
    (net (code "28") (name "MOTOR_DIR") (class "Default")
      (node (ref "PCB1") (pin "12") (pinfunction "12_12") (pintype "bidirectional"))
      (node (ref "R17") (pin "1") (pinfunction "1_1") (pintype "passive"))
      (node (ref "R18") (pin "2") (pinfunction "2_2") (pintype "passive"))
      (node (ref "U$3") (pin "P$13") (pinfunction "IN3_P$13") (pintype "input"))
      (node (ref "U$3") (pin "P$7") (pinfunction "IN1_P$7") (pintype "input"))
    )
    (net (code "29") (name "MOTOR_PWM") (class "Default")
      (node (ref "PCB1") (pin "3") (pinfunction "3_3") (pintype "bidirectional"))
      (node (ref "U$3") (pin "P$14") (pinfunction "ENB_P$14") (pintype "input"))
      (node (ref "U$3") (pin "P$8") (pinfunction "ENA_P$8") (pintype "input"))
    )
    (net (code "30") (name "MOTOR_SENSE") (class "Default")
      (node (ref "PCB1") (pin "A8") (pinfunction "A8_A8") (pintype "bidirectional"))
      (node (ref "R13") (pin "2") (pinfunction "2_2") (pintype "passive"))
      (node (ref "U2") (pin "1") (pinfunction "OUT1_1") (pintype "output"))
    )
    (net (code "31") (name "Net-(BUZZER-Pad-)") (class "Default")
      (node (ref "BUZZER") (pin "-") (pinfunction "-_-") (pintype "passive"))
      (node (ref "T1") (pin "C") (pinfunction "C_C") (pintype "passive"))
    )
    (net (code "32") (name "Net-(C16-Pad1)") (class "Default")
      (node (ref "C16") (pin "1") (pinfunction "1_1") (pintype "passive"))
      (node (ref "PCB1") (pin "RESET") (pinfunction "RESET_RESET") (pintype "bidirectional"))
    )
    (net (code "33") (name "Net-(EMERGENCY_STOP-P$1)") (class "Default")
      (node (ref "EMERGENCY_STOP") (pin "1") (pinfunction "P$1_1") (pintype "bidirectional"))
      (node (ref "FUSE") (pin "1") (pinfunction "1_1") (pintype "passive"))
    )
    (net (code "34") (name "Net-(EMERGENCY_STOP-P$2)") (class "Default")
      (node (ref "EMERGENCY_STOP") (pin "2") (pinfunction "P$2_2") (pintype "bidirectional"))
      (node (ref "JP1") (pin "1") (pinfunction "1_1") (pintype "passive"))
      (node (ref "JP1") (pin "2") (pinfunction "2_2") (pintype "passive"))
    )
    (net (code "35") (name "Net-(FLOW-Pad4)") (class "Default")
      (node (ref "FLOW") (pin "4") (pinfunction "4_4") (pintype "passive"))
      (node (ref "R9") (pin "2") (pinfunction "2_2") (pintype "passive"))
    )
    (net (code "36") (name "Net-(LED_GREEN-C)") (class "Default")
      (node (ref "LED_GREEN") (pin "K") (pinfunction "C_K") (pintype "passive"))
      (node (ref "R4") (pin "2") (pinfunction "2_2") (pintype "passive"))
    )
    (net (code "37") (name "Net-(LED_POWER-C)") (class "Default")
      (node (ref "LED_POWER") (pin "K") (pinfunction "C_K") (pintype "passive"))
      (node (ref "R3") (pin "2") (pinfunction "2_2") (pintype "passive"))
    )
    (net (code "38") (name "Net-(LED_RED-C)") (class "Default")
      (node (ref "LED_RED") (pin "K") (pinfunction "C_K") (pintype "passive"))
      (node (ref "R5") (pin "2") (pinfunction "2_2") (pintype "passive"))
    )
    (net (code "39") (name "Net-(R2-Pad1)") (class "Default")
      (node (ref "R2") (pin "1") (pinfunction "1_1") (pintype "passive"))
      (node (ref "T4") (pin "C") (pinfunction "C_C") (pintype "passive"))
    )
    (net (code "40") (name "Net-(R6-Pad2)") (class "Default")
      (node (ref "R6") (pin "2") (pinfunction "2_2") (pintype "passive"))
      (node (ref "T1") (pin "B") (pinfunction "B_B") (pintype "passive"))
    )
    (net (code "41") (name "Net-(R7-Pad2)") (class "Default")
      (node (ref "R7") (pin "2") (pinfunction "2_2") (pintype "passive"))
      (node (ref "T4") (pin "B") (pinfunction "B_B") (pintype "passive"))
    )
    (net (code "42") (name "Net-(R8-Pad2)") (class "Default")
      (node (ref "R8") (pin "2") (pinfunction "2_2") (pintype "passive"))
      (node (ref "T2") (pin "B") (pinfunction "B_B") (pintype "passive"))
    )
    (net (code "43") (name "Net-(R9-Pad1)") (class "Default")
      (node (ref "R9") (pin "1") (pinfunction "1_1") (pintype "passive"))
      (node (ref "T2") (pin "C") (pinfunction "C_C") (pintype "passive"))
    )
    (net (code "44") (name "Net-(R15-Pad2)") (class "Default")
      (node (ref "R15") (pin "2") (pinfunction "2_2") (pintype "passive"))
      (node (ref "R16") (pin "1") (pinfunction "1_1") (pintype "passive"))
    )
    (net (code "45") (name "Net-(R17-Pad2)") (class "Default")
      (node (ref "R17") (pin "2") (pinfunction "2_2") (pintype "passive"))
      (node (ref "T3") (pin "B") (pinfunction "B_B") (pintype "passive"))
    )
    (net (code "46") (name "Net-(R18-Pad1)") (class "Default")
      (node (ref "R18") (pin "1") (pinfunction "1_1") (pintype "passive"))
      (node (ref "T5") (pin "B") (pinfunction "B_B") (pintype "passive"))
    )
    (net (code "47") (name "Net-(U$3-IN2)") (class "Default")
      (node (ref "R10") (pin "2") (pinfunction "2_2") (pintype "passive"))
      (node (ref "T3") (pin "C") (pinfunction "C_C") (pintype "passive"))
      (node (ref "U$3") (pin "P$9") (pinfunction "IN2_P$9") (pintype "input"))
    )
    (net (code "48") (name "Net-(U$3-IN4)") (class "Default")
      (node (ref "R11") (pin "1") (pinfunction "1_1") (pintype "passive"))
      (node (ref "T5") (pin "C") (pinfunction "C_C") (pintype "passive"))
      (node (ref "U$3") (pin "P$15") (pinfunction "IN4_P$15") (pintype "input"))
    )
    (net (code "49") (name "Net-(U1-K)") (class "Default")
      (node (ref "R2") (pin "2") (pinfunction "2_2") (pintype "passive"))
      (node (ref "U1") (pin "16") (pinfunction "K_16") (pintype "power_in"))
    )
    (net (code "50") (name "Net-(U1-VO)") (class "Default")
      (node (ref "R1") (pin "S") (pinfunction "S_S") (pintype "passive"))
      (node (ref "U1") (pin "3") (pinfunction "VO_3") (pintype "bidirectional"))
    )
    (net (code "51") (name "Net-(VOL/ASS-CTRL-S)") (class "Default")
      (node (ref "R15") (pin "1") (pinfunction "1_1") (pintype "passive"))
      (node (ref "VOL/ASS-CTRL") (pin "3") (pinfunction "S_3") (pintype "passive"))
    )
    (net (code "52") (name "OPV_FEEDBACK") (class "Default")
      (node (ref "R13") (pin "1") (pinfunction "1_1") (pintype "passive"))
      (node (ref "R14") (pin "2") (pinfunction "2_2") (pintype "passive"))
      (node (ref "U2") (pin "2") (pinfunction "-IN1_2") (pintype "input"))
    )
    (net (code "53") (name "OUT1") (class "Default")
      (node (ref "MOTOR") (pin "1") (pinfunction "1_1") (pintype "passive"))
      (node (ref "MOTOR") (pin "2") (pinfunction "2_2") (pintype "passive"))
      (node (ref "MOTOR_CON") (pin "1") (pinfunction "1_1") (pintype "passive"))
      (node (ref "SJ1") (pin "1") (pinfunction "1_1") (pintype "passive"))
      (node (ref "U$10") (pin "P$1") (pinfunction "K_P$1") (pintype "bidirectional"))
      (node (ref "U$2") (pin "P$2") (pinfunction "A_P$2") (pintype "bidirectional"))
      (node (ref "U$3") (pin "P$4") (pinfunction "OUT1_P$4") (pintype "output"))
    )
    (net (code "54") (name "OUT2") (class "Default")
      (node (ref "MOTOR") (pin "3") (pinfunction "3_3") (pintype "passive"))
      (node (ref "MOTOR") (pin "4") (pinfunction "4_4") (pintype "passive"))
      (node (ref "MOTOR_CON") (pin "2") (pinfunction "2_2") (pintype "passive"))
      (node (ref "SJ2") (pin "1") (pinfunction "1_1") (pintype "passive"))
      (node (ref "U$3") (pin "P$5") (pinfunction "OUT2_P$5") (pintype "output"))
      (node (ref "U$4") (pin "P$2") (pinfunction "A_P$2") (pintype "bidirectional"))
      (node (ref "U$9") (pin "P$1") (pinfunction "K_P$1") (pintype "bidirectional"))
    )
    (net (code "55") (name "OUT3") (class "Default")
      (node (ref "SJ1") (pin "2") (pinfunction "2_2") (pintype "passive"))
      (node (ref "U$3") (pin "P$16") (pinfunction "OUT3_P$16") (pintype "output"))
    )
    (net (code "56") (name "OUT4") (class "Default")
      (node (ref "SJ2") (pin "2") (pinfunction "2_2") (pintype "passive"))
      (node (ref "U$3") (pin "P$17") (pinfunction "OUT4_P$17") (pintype "output"))
    )
    (net (code "57") (name "PRESSURE") (class "Default")
      (node (ref "PCB1") (pin "A5") (pinfunction "A5_A5") (pintype "bidirectional"))
      (node (ref "PRESS_SENSOR") (pin "2") (pinfunction "2_2") (pintype "passive"))
      (node (ref "U$1") (pin "4") (pinfunction "V_OUT_4") (pintype "power_in"))
    )
    (net (code "58") (name "RATE_POT") (class "Default")
      (node (ref "PCB1") (pin "A1") (pinfunction "A1_A1") (pintype "bidirectional"))
      (node (ref "RESP_RATE") (pin "S") (pinfunction "S_S") (pintype "passive"))
    )
    (net (code "59") (name "RESET") (class "Default")
      (node (ref "C16") (pin "2") (pinfunction "2_2") (pintype "passive"))
      (node (ref "PCB1") (pin "A11") (pinfunction "A11_A11") (pintype "bidirectional"))
    )
    (net (code "60") (name "SENSE") (class "Default")
      (node (ref "R12") (pin "1") (pinfunction "1_1") (pintype "passive"))
      (node (ref "U$3") (pin "P$19") (pinfunction "SENB_P$19") (pintype "input"))
      (node (ref "U$3") (pin "P$2") (pinfunction "SENA_P$2") (pintype "input"))
      (node (ref "U2") (pin "3") (pinfunction "+IN1_3") (pintype "input"))
    )
    (net (code "61") (name "SILENCE_BUTTON") (class "Default")
      (node (ref "PCB1") (pin "11") (pinfunction "11_11") (pintype "bidirectional"))
      (node (ref "SILENCE") (pin "3") (pinfunction "2_3") (pintype "passive"))
    )
    (net (code "62") (name "VOL_POT") (class "Default")
      (node (ref "PCB1") (pin "A0") (pinfunction "A0_A0") (pintype "bidirectional"))
      (node (ref "TIDAL_VOL") (pin "S") (pinfunction "S_S") (pintype "passive"))
    )
    (net (code "63") (name "unconnected-(ENCODER-Pad1)") (class "Default")
      (node (ref "ENCODER") (pin "1") (pinfunction "1_1") (pintype "passive"))
    )
    (net (code "64") (name "unconnected-(ENCODER-Pad4)") (class "Default")
      (node (ref "ENCODER") (pin "4") (pinfunction "4_4") (pintype "passive"))
    )
    (net (code "65") (name "unconnected-(PCB1-(N{slash}C)-PadN{slash}C)") (class "Default")
      (node (ref "PCB1") (pin "N/C") (pinfunction "(N/C)_N/C") (pintype "bidirectional"))
    )
    (net (code "66") (name "unconnected-(PCB1-21(SCL)-Pad21)") (class "Default")
      (node (ref "PCB1") (pin "21") (pinfunction "21(SCL)_21") (pintype "bidirectional"))
    )
    (net (code "67") (name "unconnected-(PCB1-IOREF-PadI{slash}OREF)") (class "Default")
      (node (ref "PCB1") (pin "I/OREF") (pinfunction "IOREF_I/OREF") (pintype "bidirectional"))
    )
    (net (code "68") (name "unconnected-(PCB1-Pad3.3V)") (class "Default")
      (node (ref "PCB1") (pin "3.3V") (pinfunction "3.3V_3.3V") (pintype "bidirectional"))
    )
    (net (code "69") (name "unconnected-(PCB1-PadA6)") (class "Default")
      (node (ref "PCB1") (pin "A6") (pinfunction "A6_A6") (pintype "bidirectional"))
    )
    (net (code "70") (name "unconnected-(PCB1-PadA7)") (class "Default")
      (node (ref "PCB1") (pin "A7") (pinfunction "A7_A7") (pintype "bidirectional"))
    )
    (net (code "71") (name "unconnected-(PCB1-PadA13)") (class "Default")
      (node (ref "PCB1") (pin "A13") (pinfunction "A13_A13") (pintype "bidirectional"))
    )
    (net (code "72") (name "unconnected-(PCB1-PadA14)") (class "Default")
      (node (ref "PCB1") (pin "A14") (pinfunction "A14_A14") (pintype "bidirectional"))
    )
    (net (code "73") (name "unconnected-(PCB1-PadA15)") (class "Default")
      (node (ref "PCB1") (pin "A15") (pinfunction "A15_A15") (pintype "bidirectional"))
    )
    (net (code "74") (name "unconnected-(PCB1-PadAREF)") (class "Default")
      (node (ref "PCB1") (pin "AREF") (pinfunction "AREF_AREF") (pintype "bidirectional"))
    )
    (net (code "75") (name "unconnected-(PCB1-PadSCL1)") (class "Default")
      (node (ref "PCB1") (pin "SCL1") (pinfunction "SCL1_SCL1") (pintype "bidirectional"))
    )
    (net (code "76") (name "unconnected-(PCB1-PadSDA1)") (class "Default")
      (node (ref "PCB1") (pin "SDA1") (pinfunction "SDA1_SDA1") (pintype "bidirectional"))
    )
    (net (code "77") (name "unconnected-(PCB1-PadVIN)") (class "Default")
      (node (ref "PCB1") (pin "VIN") (pinfunction "VIN_VIN") (pintype "bidirectional"))
    )
    (net (code "78") (name "unconnected-(U$3-NC1-PadP$3)") (class "Default")
      (node (ref "U$3") (pin "P$3") (pinfunction "NC1_P$3") (pintype "no_connect"))
    )
    (net (code "79") (name "unconnected-(U$3-NC2-PadP$18)") (class "Default")
      (node (ref "U$3") (pin "P$18") (pinfunction "NC2_P$18") (pintype "no_connect"))
    )
    (net (code "80") (name "unconnected-(U1-DB0-Pad7)") (class "Default")
      (node (ref "U1") (pin "7") (pinfunction "DB0_7") (pintype "bidirectional"))
    )
    (net (code "81") (name "unconnected-(U1-DB1-Pad8)") (class "Default")
      (node (ref "U1") (pin "8") (pinfunction "DB1_8") (pintype "bidirectional"))
    )
    (net (code "82") (name "unconnected-(U1-DB2-Pad9)") (class "Default")
      (node (ref "U1") (pin "9") (pinfunction "DB2_9") (pintype "bidirectional"))
    )
    (net (code "83") (name "unconnected-(U1-DB3-Pad10)") (class "Default")
      (node (ref "U1") (pin "10") (pinfunction "DB3_10") (pintype "bidirectional"))
    )
    (net (code "84") (name "unconnected-(U2-+IN2-Pad5)") (class "Default")
      (node (ref "U2") (pin "5") (pinfunction "+IN2_5") (pintype "input"))
    )
    (net (code "85") (name "unconnected-(U2-OUT2-Pad7)") (class "Default")
      (node (ref "U2") (pin "7") (pinfunction "OUT2_7") (pintype "output"))
    )
    (net (code "86") (name "~{ENC_A}") (class "Default")
      (node (ref "ENCODER") (pin "5") (pinfunction "5_5") (pintype "passive"))
      (node (ref "ENCODER_CON") (pin "3") (pinfunction "3_3") (pintype "passive"))
    )
    (net (code "87") (name "~{ENC_B}") (class "Default")
      (node (ref "ENCODER") (pin "7") (pinfunction "7_7") (pintype "passive"))
      (node (ref "ENCODER_CON") (pin "4") (pinfunction "4_4") (pintype "passive"))
    )
    (net (code "88") (name "~{ENC_I}") (class "Default")
      (node (ref "ENCODER") (pin "9") (pinfunction "9_9") (pintype "passive"))
    )
  )
)
